# Power_Management.net
KiCad netlist of a schematic drawn in Altium Designer
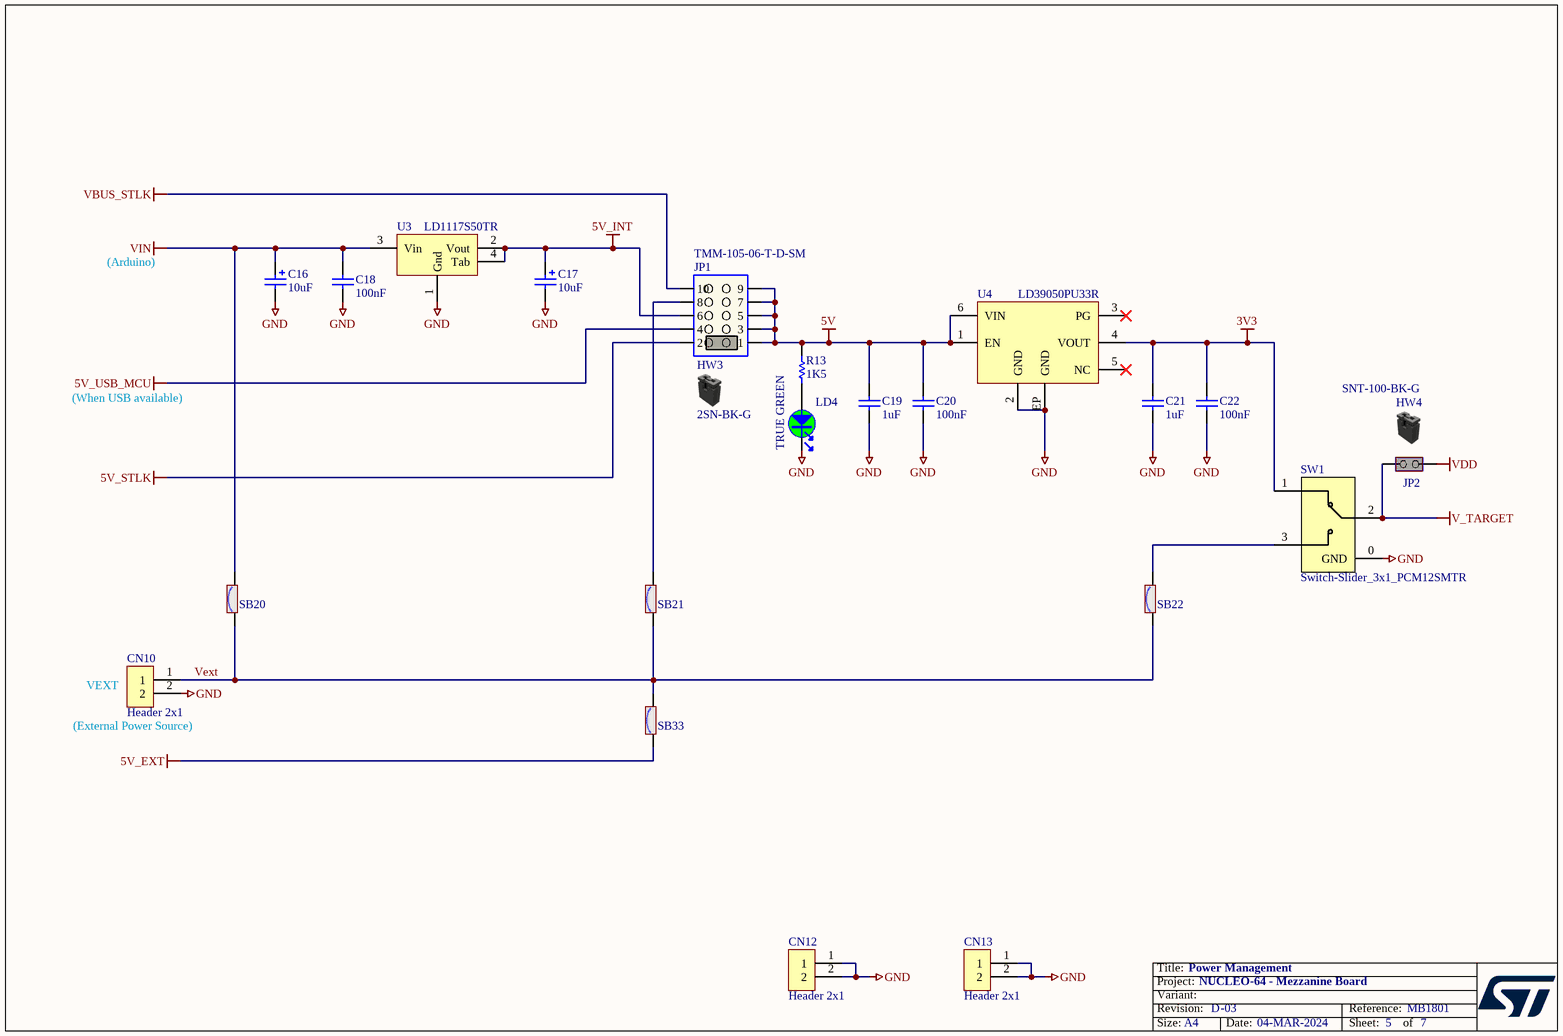
[diagram p0: Power_Management.SchDoc]

(export (version "E")
  (design (tool "Eeschema 10.0.6"))
  (components
    (comp (ref "C16")
      (value "10uF")
      (footprint "MCD_PARTS:CPOL_TAJ-B_1210_H210")
      (description "Capacitor, Tantalum, 10uF, 25V, 2R5, +/-10%, Type_B (3528 metric), T=1.9mm")
      (fields
        (field (name "INTERNAL_PART_NUMBER") "MCD-00324")
        (field (name "MANUFACTURER_PART_NUMBER") "TAJB106K025RNJ")
      )
      (libsource (lib "MCD_PARTS_database") (part "Cap_POL_TANA"))
    )
    (comp (ref "C17")
      (value "10uF")
      (footprint "MCD_PARTS:CPOL_TAJ-B_1210_H210")
      (description "Capacitor, Tantalum, 10uF, 25V, 2R5, +/-10%, Type_B (3528 metric), T=1.9mm")
      (fields
        (field (name "INTERNAL_PART_NUMBER") "MCD-00324")
        (field (name "MANUFACTURER_PART_NUMBER") "TAJB106K025RNJ")
      )
      (libsource (lib "MCD_PARTS_database") (part "Cap_POL_TANA"))
    )
    (comp (ref "C18")
      (value "100nF")
      (footprint "MCD_PARTS:C0402")
      (description "Capacitor, MLCC, 100nF, 25V, X7R, +/-10%, 0402, T=0.5mm")
      (fields (field (name "INTERNAL_PART_NUMBER") "MCD-02355") (field (name "MANUFACTURER") "WALSIN"))
      (libsource (lib "MCD_PARTS_database") (part "Capacitor"))
    )
    (comp (ref "C19")
      (value "1uF")
      (footprint "MCD_PARTS:C0805_H0P85")
      (description "Capacitor, MLCC, 1uF, 16V, X5R, +/-10%, 0805, T=0.85mm")
      (fields
        (field (name "INTERNAL_PART_NUMBER") "MCD-01550")
        (field (name "MANUFACTURER_PART_NUMBER") "CC0805KRX5R7BB105")
      )
      (libsource (lib "MCD_PARTS_database") (part "Capacitor"))
    )
    (comp (ref "C20")
      (value "100nF")
      (footprint "MCD_PARTS:C0402")
      (description "Capacitor, MLCC, 100nF, 25V, X7R, +/-10%, 0402, T=0.5mm")
      (fields (field (name "INTERNAL_PART_NUMBER") "MCD-02355") (field (name "MANUFACTURER") "WALSIN"))
      (libsource (lib "MCD_PARTS_database") (part "Capacitor"))
    )
    (comp (ref "C21")
      (value "1uF")
      (footprint "MCD_PARTS:C0805_H0P85")
      (description "Capacitor, MLCC, 1uF, 16V, X5R, +/-10%, 0805, T=0.85mm")
      (fields
        (field (name "INTERNAL_PART_NUMBER") "MCD-01550")
        (field (name "MANUFACTURER_PART_NUMBER") "CC0805KRX5R7BB105")
      )
      (libsource (lib "MCD_PARTS_database") (part "Capacitor"))
    )
    (comp (ref "C22")
      (value "100nF")
      (footprint "MCD_PARTS:C0402")
      (description "Capacitor, MLCC, 100nF, 25V, X7R, +/-10%, 0402, T=0.5mm")
      (fields (field (name "INTERNAL_PART_NUMBER") "MCD-02355") (field (name "MANUFACTURER") "WALSIN"))
      (libsource (lib "MCD_PARTS_database") (part "Capacitor"))
    )
    (comp (ref "CN10")
      (value "Header 2x1")
      (footprint "MCD_PARTS:CON_SAMTEC_TSW-102-07-G-S")
      (description "Header, 2x1, 2.54mm, VR, TH, T=5.84mm/2.54mm")
      (fields (field (name "INTERNAL_PART_NUMBER") "MCD-00032") (field (name "MANUFACTURER") "SAMTEC"))
      (libsource (lib "MCD_PARTS_database") (part "Header 2x1"))
    )
    (comp (ref "CN12")
      (value "Header 2x1")
      (footprint "MCD_PARTS:CON_SAMTEC_TSW-102-07-G-S")
      (description "Header, 2x1, 2.54mm, VR, TH, T=5.84mm/2.54mm")
      (fields (field (name "INTERNAL_PART_NUMBER") "MCD-00032") (field (name "MANUFACTURER") "SAMTEC"))
      (libsource (lib "MCD_PARTS_database") (part "Header 2x1"))
    )
    (comp (ref "CN13")
      (value "Header 2x1")
      (footprint "MCD_PARTS:CON_SAMTEC_TSW-102-07-G-S")
      (description "Header, 2x1, 2.54mm, VR, TH, T=5.84mm/2.54mm")
      (fields (field (name "INTERNAL_PART_NUMBER") "MCD-00032") (field (name "MANUFACTURER") "SAMTEC"))
      (libsource (lib "MCD_PARTS_database") (part "Header 2x1"))
    )
    (comp (ref "HW3")
      (value "2SN-BK-G")
      (description "Shunt, 2,00mm, black")
      (fields (field (name "INTERNAL_PART_NUMBER") "MCD-03319") (field (name "MANUFACTURER") "SAMTEC"))
      (libsource (lib "MCD_PARTS_database") (part "2SN-BK-G"))
    )
    (comp (ref "HW4")
      (value "SNT-100-BK-G")
      (description "SHUNT 2.54mm BLACK")
      (fields (field (name "INTERNAL_PART_NUMBER") "MCD-00043") (field (name "MANUFACTURER") "SAMTEC"))
      (libsource (lib "MCD_PARTS_database") (part "Shunt Black 2.54mm"))
    )
    (comp (ref "JP1")
      (value "TMM-105-06-T-D-SM")
      (footprint "MCD_PARTS:CON_SAMTEC_TMM-105-06-T-D-SM")
      (description "Header, 10x2, 2,00mm, h=7,04mm, VR, SMD")
      (fields (field (name "INTERNAL_PART_NUMBER") "MCD-03317") (field (name "MANUFACTURER") "SAMTEC"))
      (libsource (lib "MCD_PARTS_database") (part "TMM-105-06-T-D-SM"))
    )
    (comp (ref "JP2")
      (value "Jumper_Header 2x1 Fitted")
      (footprint "MCD_PARTS:CON_SAMTEC_TSW-102-07-G-S")
      (description "Header, 2x1, 2.54mm, VR, TH, T=5.84mm/2.54mm")
      (fields
        (field (name "INTERNAL_PART_NUMBER") "MCD-01904")
        (field (name "MANUFACTURER_PART_NUMBER") "TSW-102-07-G-S")
      )
      (libsource (lib "MCD_PARTS_database") (part "Jumper_Header 2x1 Fitted"))
    )
    (comp (ref "LD4")
      (value "TRUE GREEN")
      (footprint "MCD_PARTS:LED_0603_VISHAY_VLMTG1300-GS08_GREEN_1A2K_H0P8")
      (description "LED Green, 0603 SMD, Fw Voltage = 2.8V - 3.6V")
      (fields
        (field (name "INTERNAL_PART_NUMBER") "MCD-00589")
        (field (name "MANUFACTURER_PART_NUMBER") "VLMTG1300-GS08")
      )
      (libsource (lib "MCD_PARTS_database") (part "LED_green"))
    )
    (comp (ref "R13")
      (value "1K5")
      (footprint "R0402")
      (description "Resistor, 1K5, 0402, +/-1%, 1/16W")
      (fields (field (name "INTERNAL_PART_NUMBER") "MCD-00068") (field (name "MANUFACTURER") "YAGEO"))
      (libsource (lib "MCD_PARTS_database") (part "Resistor"))
    )
    (comp (ref "SB20")
      (value "SB_ON")
      (footprint "MCD_PARTS:SOLDER-BRIDGE_R0402-0R")
      (description "Solder Bridge 0402 ON")
      (fields (field (name "INTERNAL_PART_NUMBER") "MCD-01618") (field (name "MANUFACTURER") "YAGEO"))
      (libsource (lib "MCD_PARTS_database") (part "SB_ON"))
    )
    (comp (ref "SB21")
      (value "SB_ON")
      (footprint "MCD_PARTS:SOLDER-BRIDGE_R0402-0R")
      (description "Solder Bridge 0402 ON")
      (fields (field (name "INTERNAL_PART_NUMBER") "MCD-01618") (field (name "MANUFACTURER") "YAGEO"))
      (libsource (lib "MCD_PARTS_database") (part "SB_ON"))
    )
    (comp (ref "SB22")
      (value "SB_ON")
      (footprint "MCD_PARTS:SOLDER-BRIDGE_R0402-0R")
      (description "Solder Bridge 0402 ON")
      (fields (field (name "INTERNAL_PART_NUMBER") "MCD-01618") (field (name "MANUFACTURER") "YAGEO"))
      (libsource (lib "MCD_PARTS_database") (part "SB_ON"))
    )
    (comp (ref "SB33")
      (value "SB_ON")
      (footprint "MCD_PARTS:SOLDER-BRIDGE_R0402-0R")
      (description "Solder Bridge 0402 ON")
      (fields (field (name "INTERNAL_PART_NUMBER") "MCD-01618") (field (name "MANUFACTURER") "YAGEO"))
      (libsource (lib "MCD_PARTS_database") (part "SB_ON"))
    )
    (comp (ref "SW1")
      (value "Switch-Slider_3x1_PCM12SMTR")
      (footprint "MCD_PARTS:SWI_SPDT-RA_TE-CONNECTIVITY_MLL1200S_1P2T")
      (description "Slide switch, 3x1, 1.5mm, RA, SMT, T=1.65mm")
      (fields (field (name "INTERNAL_PART_NUMBER") "MCD-03571") (field (name "MANUFACTURER") "C&K"))
      (libsource (lib "MCD_PARTS_database") (part "SW_MECA"))
    )
    (comp (ref "U3")
      (value "LD1117S50TR")
      (footprint "MCD_PARTS:REG_SOT223-TAB")
      (description "IC REG LDO 5V 0.8A SOT223")
      (fields
        (field (name "INTERNAL_PART_NUMBER") "MCD-00088")
        (field (name "MANUFACTURER") "STMICROELECTRONICS")
      )
      (libsource (lib "MCD_PARTS_database") (part "LD1117S50TR"))
    )
    (comp (ref "U4")
      (value "LD39050PU33R")
      (footprint "MCD_PARTS:ICC_DFN6-EPAD_3X3_P095")
      (description "Low quiescent current and low noise voltage regulators")
      (fields
        (field (name "INTERNAL_PART_NUMBER") "MCD-00215")
        (field (name "MANUFACTURER") "STMICROELECTRONICS")
      )
      (libsource (lib "MCD_PARTS_database") (part "LD39050PU33R"))
    )
  )
  (nets
    (net (code "1") (name "/Vext") (class "Default")
      (node (ref "CN10") (pin "1") (pinfunction "1_1") (pintype "passive"))
      (node (ref "SB20") (pin "1") (pinfunction "1_1") (pintype "passive"))
      (node (ref "SB21") (pin "1") (pinfunction "1_1") (pintype "passive"))
      (node (ref "SB22") (pin "1") (pinfunction "1_1") (pintype "passive"))
      (node (ref "SB33") (pin "2") (pinfunction "2_2") (pintype "passive"))
    )
    (net (code "2") (name "3V3") (class "Default")
      (node (ref "C21") (pin "2") (pinfunction "2_2") (pintype "passive"))
      (node (ref "C22") (pin "2") (pinfunction "2_2") (pintype "passive"))
      (node (ref "SW1") (pin "1") (pinfunction "1_1") (pintype "passive"))
      (node (ref "U4") (pin "4") (pinfunction "VOUT_4") (pintype "passive"))
    )
    (net (code "3") (name "5V") (class "Default")
      (node (ref "C19") (pin "2") (pinfunction "2_2") (pintype "passive"))
      (node (ref "C20") (pin "2") (pinfunction "2_2") (pintype "passive"))
      (node (ref "JP1") (pin "1") (pinfunction "1_1") (pintype "passive"))
      (node (ref "JP1") (pin "3") (pinfunction "3_3") (pintype "passive"))
      (node (ref "JP1") (pin "5") (pinfunction "5_5") (pintype "passive"))
      (node (ref "JP1") (pin "7") (pinfunction "7_7") (pintype "passive"))
      (node (ref "JP1") (pin "9") (pinfunction "9_9") (pintype "passive"))
      (node (ref "R13") (pin "2") (pinfunction "2_2") (pintype "passive"))
      (node (ref "U4") (pin "1") (pinfunction "EN_1") (pintype "passive"))
      (node (ref "U4") (pin "6") (pinfunction "VIN_6") (pintype "passive"))
    )
    (net (code "4") (name "5V_EXT") (class "Default")
      (node (ref "SB33") (pin "1") (pinfunction "1_1") (pintype "passive"))
    )
    (net (code "5") (name "5V_INT") (class "Default")
      (node (ref "C17") (pin "1") (pinfunction "1_1") (pintype "passive"))
      (node (ref "JP1") (pin "6") (pinfunction "6_6") (pintype "passive"))
      (node (ref "U3") (pin "2") (pinfunction "Vout_2") (pintype "passive"))
      (node (ref "U3") (pin "4") (pinfunction "Tab_4") (pintype "passive"))
    )
    (net (code "6") (name "5V_STLK") (class "Default")
      (node (ref "JP1") (pin "2") (pinfunction "2_2") (pintype "passive"))
    )
    (net (code "7") (name "5V_USB_MCU") (class "Default")
      (node (ref "JP1") (pin "4") (pinfunction "4_4") (pintype "passive"))
    )
    (net (code "8") (name "GND") (class "Default")
      (node (ref "C16") (pin "2") (pinfunction "2_2") (pintype "passive"))
      (node (ref "C17") (pin "2") (pinfunction "2_2") (pintype "passive"))
      (node (ref "C18") (pin "1") (pinfunction "1_1") (pintype "passive"))
      (node (ref "C19") (pin "1") (pinfunction "1_1") (pintype "passive"))
      (node (ref "C20") (pin "1") (pinfunction "1_1") (pintype "passive"))
      (node (ref "C21") (pin "1") (pinfunction "1_1") (pintype "passive"))
      (node (ref "C22") (pin "1") (pinfunction "1_1") (pintype "passive"))
      (node (ref "CN10") (pin "2") (pinfunction "2_2") (pintype "passive"))
      (node (ref "CN12") (pin "1") (pinfunction "1_1") (pintype "passive"))
      (node (ref "CN12") (pin "2") (pinfunction "2_2") (pintype "passive"))
      (node (ref "CN13") (pin "1") (pinfunction "1_1") (pintype "passive"))
      (node (ref "CN13") (pin "2") (pinfunction "2_2") (pintype "passive"))
      (node (ref "LD4") (pin "2") (pintype "passive"))
      (node (ref "SW1") (pin "0") (pinfunction "GND_0") (pintype "passive"))
      (node (ref "U3") (pin "1") (pinfunction "Gnd_1") (pintype "passive"))
      (node (ref "U4") (pin "2") (pinfunction "GND_2") (pintype "passive"))
      (node (ref "U4") (pin "EP") (pinfunction "GND_EP") (pintype "passive"))
    )
    (net (code "9") (name "Net-(JP1-Pad8)") (class "Default")
      (node (ref "JP1") (pin "8") (pinfunction "8_8") (pintype "passive"))
      (node (ref "SB21") (pin "2") (pinfunction "2_2") (pintype "passive"))
    )
    (net (code "10") (name "Net-(LD4-Pad1)") (class "Default")
      (node (ref "LD4") (pin "1") (pintype "passive"))
      (node (ref "R13") (pin "1") (pinfunction "1_1") (pintype "passive"))
    )
    (net (code "11") (name "Net-(SB22-Pad2)") (class "Default")
      (node (ref "SB22") (pin "2") (pinfunction "2_2") (pintype "passive"))
      (node (ref "SW1") (pin "3") (pinfunction "3_3") (pintype "passive"))
    )
    (net (code "12") (name "VBUS_STLK") (class "Default")
      (node (ref "JP1") (pin "10") (pinfunction "10_10") (pintype "passive"))
    )
    (net (code "13") (name "VDD") (class "Default")
      (node (ref "JP2") (pin "2") (pinfunction "NO_2") (pintype "passive"))
    )
    (net (code "14") (name "VIN") (class "Default")
      (node (ref "C16") (pin "1") (pinfunction "1_1") (pintype "passive"))
      (node (ref "C18") (pin "2") (pinfunction "2_2") (pintype "passive"))
      (node (ref "SB20") (pin "2") (pinfunction "2_2") (pintype "passive"))
      (node (ref "U3") (pin "3") (pinfunction "Vin_3") (pintype "passive"))
    )
    (net (code "15") (name "V_TARGET") (class "Default")
      (node (ref "JP2") (pin "1") (pinfunction "COMMON_1") (pintype "passive"))
      (node (ref "SW1") (pin "2") (pinfunction "2_2") (pintype "passive"))
    )
    (net (code "16") (name "unconnected-(U4-NC-Pad5)") (class "Default")
      (node (ref "U4") (pin "5") (pinfunction "NC_5") (pintype "passive+no_connect"))
    )
    (net (code "17") (name "unconnected-(U4-PG-Pad3)") (class "Default")
      (node (ref "U4") (pin "3") (pinfunction "PG_3") (pintype "passive+no_connect"))
    )
  )
)
